# imuv1_3.net
KiCad netlist of a schematic drawn in EAGLE
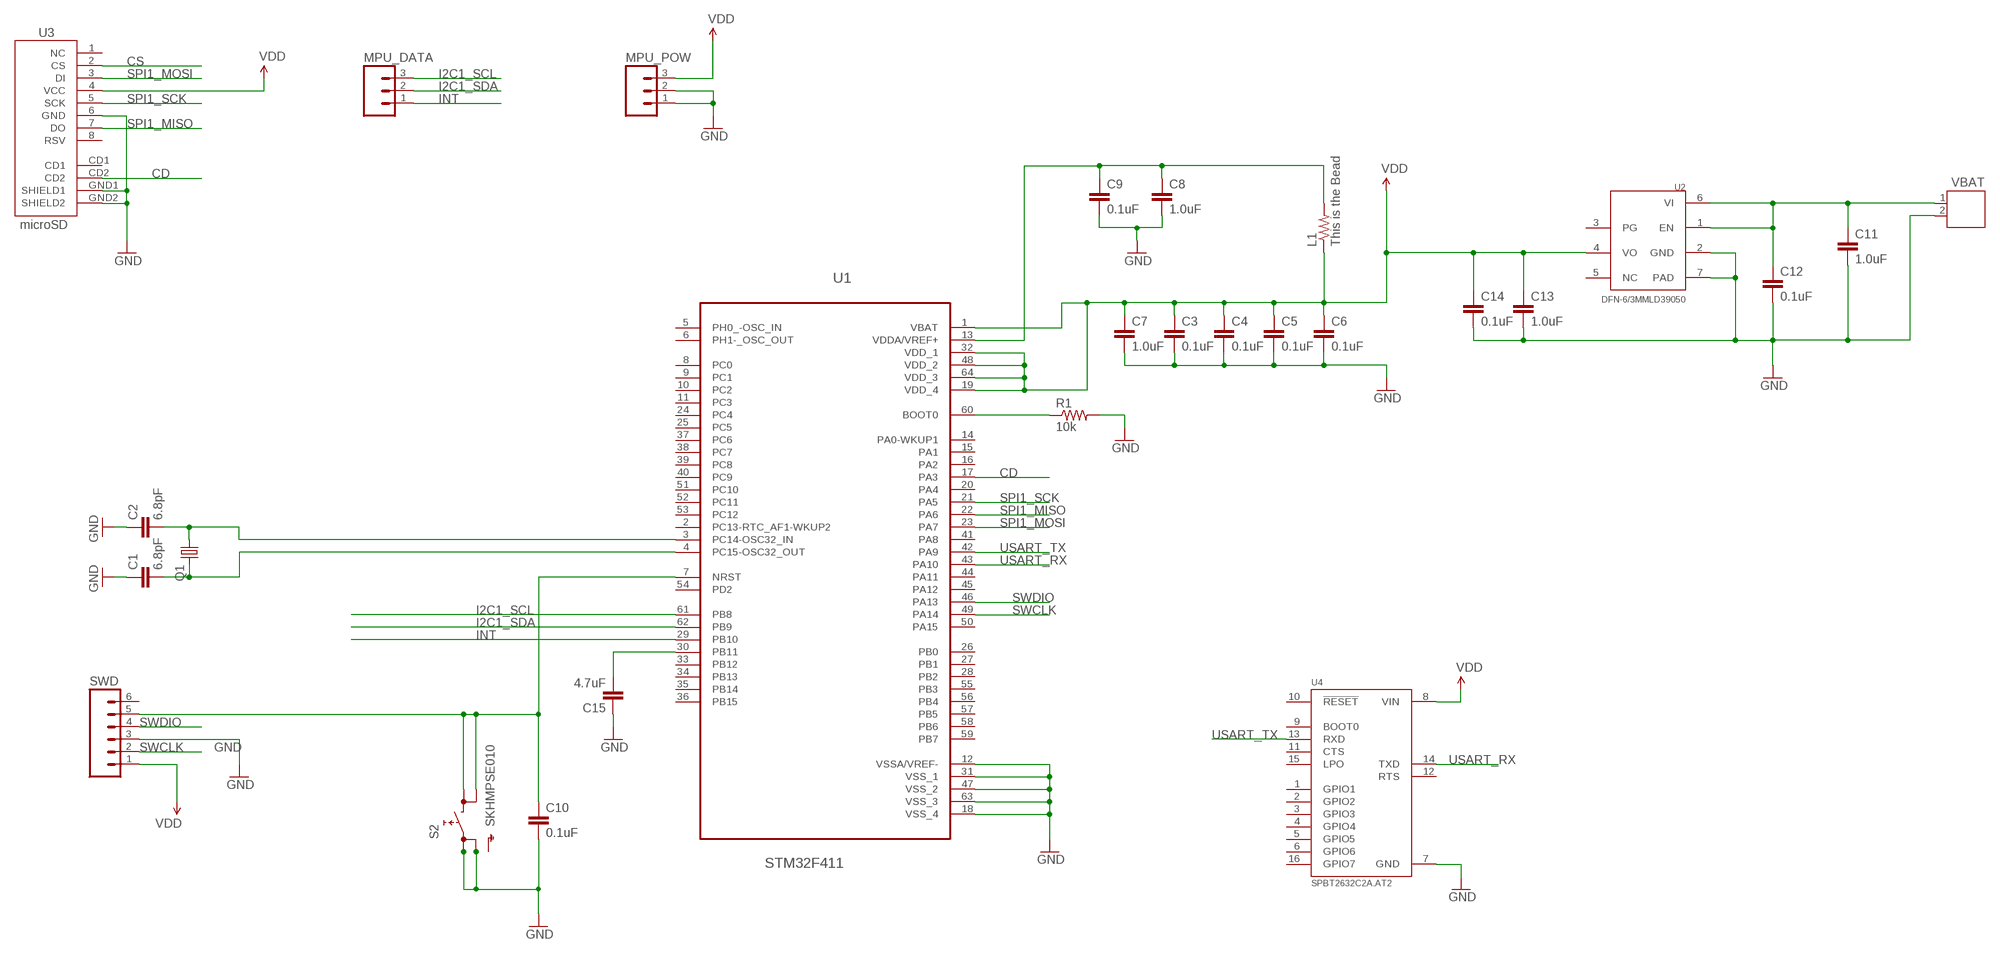
[diagram p0: schematic, sheet 1]

(export (version "E")
  (design (tool "Eeschema 10.0.6"))
  (components
    (comp (ref "C1")
      (value "6.8pF")
      (footprint "eagle-import:0603-CAP")
      (libsource (lib "eagle-import") (part "1.0PF-50V(-/+.25PF)(0603)"))
    )
    (comp (ref "C2")
      (value "6.8pF")
      (footprint "eagle-import:0603-CAP")
      (libsource (lib "eagle-import") (part "1.0PF-50V(-/+.25PF)(0603)"))
    )
    (comp (ref "C3")
      (value "0.1uF")
      (footprint "eagle-import:0603-CAP")
      (libsource (lib "eagle-import") (part "0.1UF-100V-10%(0603)"))
    )
    (comp (ref "C4")
      (value "0.1uF")
      (footprint "eagle-import:0603-CAP")
      (libsource (lib "eagle-import") (part "0.1UF-100V-10%(0603)"))
    )
    (comp (ref "C5")
      (value "0.1uF")
      (footprint "eagle-import:0603-CAP")
      (libsource (lib "eagle-import") (part "0.1UF-100V-10%(0603)"))
    )
    (comp (ref "C6")
      (value "0.1uF")
      (footprint "eagle-import:0603-CAP")
      (libsource (lib "eagle-import") (part "0.1UF-100V-10%(0603)"))
    )
    (comp (ref "C7")
      (value "1.0uF")
      (footprint "eagle-import:0603-CAP")
      (libsource (lib "eagle-import") (part "1.0UF-16V-10%(0603)"))
    )
    (comp (ref "C8")
      (value "1.0uF")
      (footprint "eagle-import:0603-CAP")
      (libsource (lib "eagle-import") (part "1.0UF-16V-10%(0603)"))
    )
    (comp (ref "C9")
      (value "0.1uF")
      (footprint "eagle-import:0603-CAP")
      (libsource (lib "eagle-import") (part "0.1UF-100V-10%(0603)"))
    )
    (comp (ref "C10")
      (value "0.1uF")
      (footprint "eagle-import:0603-CAP")
      (libsource (lib "eagle-import") (part "0.1UF-100V-10%(0603)"))
    )
    (comp (ref "C11")
      (value "1.0uF")
      (footprint "eagle-import:0603-CAP")
      (libsource (lib "eagle-import") (part "1.0UF-16V-10%(0603)"))
    )
    (comp (ref "C12")
      (value "0.1uF")
      (footprint "eagle-import:0603-CAP")
      (libsource (lib "eagle-import") (part "0.1UF-100V-10%(0603)"))
    )
    (comp (ref "C13")
      (value "1.0uF")
      (footprint "eagle-import:0603-CAP")
      (libsource (lib "eagle-import") (part "1.0UF-16V-10%(0603)"))
    )
    (comp (ref "C14")
      (value "0.1uF")
      (footprint "eagle-import:0603-CAP")
      (libsource (lib "eagle-import") (part "0.1UF-100V-10%(0603)"))
    )
    (comp (ref "C15")
      (value "4.7uF")
      (footprint "eagle-import:1206-CAP")
      (libsource (lib "eagle-import") (part "4.7UF-16V-20%,+80%-(1206)"))
    )
    (comp (ref "L1")
      (value "This is the Bead")
      (footprint "eagle-import:0603-RES")
      (libsource (lib "eagle-import") (part "1OHM1/10W1%(0603)"))
    )
    (comp (ref "MPU_DATA")
      (value "M03PTH")
      (footprint "eagle-import:1X03")
      (libsource (lib "eagle-import") (part "M03PTH"))
    )
    (comp (ref "MPU_POW")
      (value "M03PTH")
      (footprint "eagle-import:1X03")
      (libsource (lib "eagle-import") (part "M03PTH"))
    )
    (comp (ref "Q1")
      (value "CRYSTALMM20SS")
      (footprint "eagle-import:MM20SS")
      (libsource (lib "eagle-import") (part "CRYSTALMM20SS"))
    )
    (comp (ref "R1")
      (value "10k")
      (footprint "eagle-import:0603-RES")
      (libsource (lib "eagle-import") (part "470OHM1/10W1%(0603)"))
    )
    (comp (ref "S2")
      (value "SKHMPSE010")
      (footprint "eagle-import:SKHMPXE010")
      (libsource (lib "eagle-import") (part "SKHMPE010S"))
    )
    (comp (ref "SWD")
      (value "M06SILK_FEMALE_PTH")
      (footprint "eagle-import:1X06")
      (libsource (lib "eagle-import") (part "M06SILK_FEMALE_PTH"))
    )
    (comp (ref "U1")
      (value "STM32F411")
      (footprint "eagle-import:QFP50P1200X1200X160-64N")
      (libsource (lib "eagle-import") (part "STM32L152RBT6STM32F411"))
    )
    (comp (ref "U2")
      (value "DFN-6/3MMLD39050")
      (footprint "eagle-import:DFN-6_3MM")
      (libsource (lib "eagle-import") (part "DFN-6/3MMLD39050"))
    )
    (comp (ref "U3")
      (value "microSD")
      (footprint "eagle-import:MICRO-SD-SOCKET-PP")
      (libsource (lib "eagle-import") (part "USD-SOCKETSMD"))
    )
    (comp (ref "U4")
      (value "SPBT2632C2A.AT2")
      (footprint "eagle-import:XCVR_SPBT2632C2A.AT2")
      (libsource (lib "eagle-import") (part "SPBT2632C2A.AT2"))
    )
    (comp (ref "VBAT")
      (value "JST-PH2")
      (footprint "eagle-import:JST-PH2")
      (libsource (lib "eagle-import") (part "JST-PH2"))
    )
  )
  (nets
    (net (code "1") (name "/CD") (class "Default")
      (node (ref "U1") (pin "17") (pinfunction "PA3_17") (pintype "bidirectional"))
      (node (ref "U3") (pin "CD2") (pinfunction "CD2_CD2") (pintype "bidirectional"))
    )
    (net (code "2") (name "/CS") (class "Default")
      (node (ref "U3") (pin "2") (pinfunction "CS_2") (pintype "bidirectional"))
    )
    (net (code "3") (name "/I2C1_SCL") (class "Default")
      (node (ref "MPU_DATA") (pin "3") (pinfunction "3_3") (pintype "passive"))
      (node (ref "U1") (pin "61") (pinfunction "PB8_61") (pintype "bidirectional"))
    )
    (net (code "4") (name "/I2C1_SDA") (class "Default")
      (node (ref "MPU_DATA") (pin "2") (pinfunction "2_2") (pintype "passive"))
      (node (ref "U1") (pin "62") (pinfunction "PB9_62") (pintype "bidirectional"))
    )
    (net (code "5") (name "/INT") (class "Default")
      (node (ref "MPU_DATA") (pin "1") (pinfunction "1_1") (pintype "passive"))
      (node (ref "U1") (pin "29") (pinfunction "PB10_29") (pintype "bidirectional"))
    )
    (net (code "6") (name "/NC") (class "Default")
      (node (ref "U2") (pin "5") (pinfunction "NC_5") (pintype "power_in"))
    )
    (net (code "7") (name "/PG") (class "Default")
      (node (ref "U2") (pin "3") (pinfunction "PG_3") (pintype "power_in"))
    )
    (net (code "8") (name "/SPI1_MISO") (class "Default")
      (node (ref "U1") (pin "22") (pinfunction "PA6_22") (pintype "bidirectional"))
      (node (ref "U3") (pin "7") (pinfunction "DO_7") (pintype "bidirectional"))
    )
    (net (code "9") (name "/SPI1_MOSI") (class "Default")
      (node (ref "U1") (pin "23") (pinfunction "PA7_23") (pintype "bidirectional"))
      (node (ref "U3") (pin "3") (pinfunction "DI_3") (pintype "bidirectional"))
    )
    (net (code "10") (name "/SPI1_SCK") (class "Default")
      (node (ref "U1") (pin "21") (pinfunction "PA5_21") (pintype "bidirectional"))
      (node (ref "U3") (pin "5") (pinfunction "SCK_5") (pintype "bidirectional"))
    )
    (net (code "11") (name "/SWCLK") (class "Default")
      (node (ref "SWD") (pin "2") (pinfunction "2_2") (pintype "passive"))
      (node (ref "U1") (pin "49") (pinfunction "PA14_49") (pintype "bidirectional"))
    )
    (net (code "12") (name "/SWDIO") (class "Default")
      (node (ref "SWD") (pin "4") (pinfunction "4_4") (pintype "passive"))
      (node (ref "U1") (pin "46") (pinfunction "PA13_46") (pintype "bidirectional"))
    )
    (net (code "13") (name "/USART_RX") (class "Default")
      (node (ref "U1") (pin "43") (pinfunction "PA10_43") (pintype "bidirectional"))
      (node (ref "U4") (pin "14") (pinfunction "TXD_14") (pintype "output"))
    )
    (net (code "14") (name "/USART_TX") (class "Default")
      (node (ref "U1") (pin "42") (pinfunction "PA9_42") (pintype "bidirectional"))
      (node (ref "U4") (pin "13") (pinfunction "RXD_13") (pintype "input"))
    )
    (net (code "15") (name "GND") (class "Default")
      (node (ref "C1") (pin "1") (pinfunction "1_1") (pintype "passive"))
      (node (ref "C10") (pin "2") (pinfunction "2_2") (pintype "passive"))
      (node (ref "C11") (pin "2") (pinfunction "2_2") (pintype "passive"))
      (node (ref "C12") (pin "2") (pinfunction "2_2") (pintype "passive"))
      (node (ref "C13") (pin "2") (pinfunction "2_2") (pintype "passive"))
      (node (ref "C14") (pin "2") (pinfunction "2_2") (pintype "passive"))
      (node (ref "C15") (pin "1") (pinfunction "1_1") (pintype "passive"))
      (node (ref "C2") (pin "1") (pinfunction "1_1") (pintype "passive"))
      (node (ref "C3") (pin "2") (pinfunction "2_2") (pintype "passive"))
      (node (ref "C4") (pin "2") (pinfunction "2_2") (pintype "passive"))
      (node (ref "C5") (pin "2") (pinfunction "2_2") (pintype "passive"))
      (node (ref "C6") (pin "2") (pinfunction "2_2") (pintype "passive"))
      (node (ref "C7") (pin "2") (pinfunction "2_2") (pintype "passive"))
      (node (ref "C8") (pin "2") (pinfunction "2_2") (pintype "passive"))
      (node (ref "C9") (pin "2") (pinfunction "2_2") (pintype "passive"))
      (node (ref "MPU_POW") (pin "1") (pinfunction "1_1") (pintype "passive"))
      (node (ref "MPU_POW") (pin "2") (pinfunction "2_2") (pintype "passive"))
      (node (ref "R1") (pin "2") (pinfunction "2_2") (pintype "passive"))
      (node (ref "S2") (pin "1") (pinfunction "1.1_1") (pintype "passive"))
      (node (ref "S2") (pin "2") (pinfunction "1.2_2") (pintype "passive"))
      (node (ref "SWD") (pin "3") (pinfunction "3_3") (pintype "passive"))
      (node (ref "U1") (pin "12") (pinfunction "VSSA/VREF-_12") (pintype "power_in"))
      (node (ref "U1") (pin "18") (pinfunction "VSS_4_18") (pintype "power_in"))
      (node (ref "U1") (pin "31") (pinfunction "VSS_1_31") (pintype "power_in"))
      (node (ref "U1") (pin "47") (pinfunction "VSS_2_47") (pintype "power_in"))
      (node (ref "U1") (pin "63") (pinfunction "VSS_3_63") (pintype "power_in"))
      (node (ref "U2") (pin "2") (pinfunction "GND_2") (pintype "power_in"))
      (node (ref "U2") (pin "7") (pinfunction "PAD_7") (pintype "power_in"))
      (node (ref "U3") (pin "6") (pinfunction "GND_6") (pintype "bidirectional"))
      (node (ref "U3") (pin "GND1") (pinfunction "SHIELD1_GND1") (pintype "bidirectional"))
      (node (ref "U3") (pin "GND2") (pinfunction "SHIELD2_GND2") (pintype "bidirectional"))
      (node (ref "U4") (pin "7") (pinfunction "GND_7") (pintype "power_in"))
      (node (ref "VBAT") (pin "2") (pinfunction "2_2") (pintype "passive"))
    )
    (net (code "16") (name "Net-(Q1-2)") (class "Default")
      (node (ref "C1") (pin "2") (pinfunction "2_2") (pintype "passive"))
      (node (ref "Q1") (pin "4") (pinfunction "2_4") (pintype "passive"))
      (node (ref "U1") (pin "4") (pinfunction "PC15-OSC32_OUT_4") (pintype "bidirectional"))
    )
    (net (code "17") (name "Net-(S2-2.1)") (class "Default")
      (node (ref "C10") (pin "1") (pinfunction "1_1") (pintype "passive"))
      (node (ref "S2") (pin "3") (pinfunction "2.1_3") (pintype "passive"))
      (node (ref "S2") (pin "4") (pinfunction "2.2_4") (pintype "passive"))
      (node (ref "SWD") (pin "5") (pinfunction "5_5") (pintype "passive"))
      (node (ref "U1") (pin "7") (pinfunction "NRST_7") (pintype "bidirectional"))
    )
    (net (code "18") (name "Net-(U1-BOOT0)") (class "Default")
      (node (ref "R1") (pin "1") (pinfunction "1_1") (pintype "passive"))
      (node (ref "U1") (pin "60") (pinfunction "BOOT0_60") (pintype "input"))
    )
    (net (code "19") (name "Net-(U1-PB11)") (class "Default")
      (node (ref "C15") (pin "2") (pinfunction "2_2") (pintype "passive"))
      (node (ref "U1") (pin "30") (pinfunction "PB11_30") (pintype "bidirectional"))
    )
    (net (code "20") (name "Net-(U1-PC14-OSC32_IN)") (class "Default")
      (node (ref "C2") (pin "2") (pinfunction "2_2") (pintype "passive"))
      (node (ref "Q1") (pin "1") (pinfunction "1_1") (pintype "passive"))
      (node (ref "U1") (pin "3") (pinfunction "PC14-OSC32_IN_3") (pintype "bidirectional"))
    )
    (net (code "21") (name "Net-(U1-VDDA{slash}VREF+)") (class "Default")
      (node (ref "C8") (pin "1") (pinfunction "1_1") (pintype "passive"))
      (node (ref "C9") (pin "1") (pinfunction "1_1") (pintype "passive"))
      (node (ref "L1") (pin "2") (pinfunction "2_2") (pintype "passive"))
      (node (ref "U1") (pin "13") (pinfunction "VDDA/VREF+_13") (pintype "power_in"))
    )
    (net (code "22") (name "Net-(U2-EN)") (class "Default")
      (node (ref "C11") (pin "1") (pinfunction "1_1") (pintype "passive"))
      (node (ref "C12") (pin "1") (pinfunction "1_1") (pintype "passive"))
      (node (ref "U2") (pin "1") (pinfunction "EN_1") (pintype "power_in"))
      (node (ref "U2") (pin "6") (pinfunction "VI_6") (pintype "power_in"))
      (node (ref "VBAT") (pin "1") (pinfunction "1_1") (pintype "passive"))
    )
    (net (code "23") (name "VDD") (class "Default")
      (node (ref "C13") (pin "1") (pinfunction "1_1") (pintype "passive"))
      (node (ref "C14") (pin "1") (pinfunction "1_1") (pintype "passive"))
      (node (ref "C3") (pin "1") (pinfunction "1_1") (pintype "passive"))
      (node (ref "C4") (pin "1") (pinfunction "1_1") (pintype "passive"))
      (node (ref "C5") (pin "1") (pinfunction "1_1") (pintype "passive"))
      (node (ref "C6") (pin "1") (pinfunction "1_1") (pintype "passive"))
      (node (ref "C7") (pin "1") (pinfunction "1_1") (pintype "passive"))
      (node (ref "L1") (pin "1") (pinfunction "1_1") (pintype "passive"))
      (node (ref "MPU_POW") (pin "3") (pinfunction "3_3") (pintype "passive"))
      (node (ref "SWD") (pin "1") (pinfunction "1_1") (pintype "passive"))
      (node (ref "U1") (pin "1") (pinfunction "VBAT_1") (pintype "power_in"))
      (node (ref "U1") (pin "19") (pinfunction "VDD_4_19") (pintype "power_in"))
      (node (ref "U1") (pin "32") (pinfunction "VDD_1_32") (pintype "power_in"))
      (node (ref "U1") (pin "48") (pinfunction "VDD_2_48") (pintype "power_in"))
      (node (ref "U1") (pin "64") (pinfunction "VDD_3_64") (pintype "power_in"))
      (node (ref "U2") (pin "4") (pinfunction "VO_4") (pintype "power_in"))
      (node (ref "U3") (pin "4") (pinfunction "VCC_4") (pintype "bidirectional"))
      (node (ref "U4") (pin "8") (pinfunction "VIN_8") (pintype "power_in"))
    )
    (net (code "24") (name "unconnected-(S2-SH-Pad5)") (class "Default")
      (node (ref "S2") (pin "5") (pinfunction "SH_5") (pintype "passive"))
    )
    (net (code "25") (name "unconnected-(SWD-Pad6)") (class "Default")
      (node (ref "SWD") (pin "6") (pinfunction "6_6") (pintype "passive"))
    )
    (net (code "26") (name "unconnected-(U1-PA0-WKUP1-Pad14)") (class "Default")
      (node (ref "U1") (pin "14") (pinfunction "PA0-WKUP1_14") (pintype "bidirectional"))
    )
    (net (code "27") (name "unconnected-(U1-PA1-Pad15)") (class "Default")
      (node (ref "U1") (pin "15") (pinfunction "PA1_15") (pintype "bidirectional"))
    )
    (net (code "28") (name "unconnected-(U1-PA2-Pad16)") (class "Default")
      (node (ref "U1") (pin "16") (pinfunction "PA2_16") (pintype "bidirectional"))
    )
    (net (code "29") (name "unconnected-(U1-PA4-Pad20)") (class "Default")
      (node (ref "U1") (pin "20") (pinfunction "PA4_20") (pintype "bidirectional"))
    )
    (net (code "30") (name "unconnected-(U1-PA8-Pad41)") (class "Default")
      (node (ref "U1") (pin "41") (pinfunction "PA8_41") (pintype "bidirectional"))
    )
    (net (code "31") (name "unconnected-(U1-PA11-Pad44)") (class "Default")
      (node (ref "U1") (pin "44") (pinfunction "PA11_44") (pintype "bidirectional"))
    )
    (net (code "32") (name "unconnected-(U1-PA12-Pad45)") (class "Default")
      (node (ref "U1") (pin "45") (pinfunction "PA12_45") (pintype "bidirectional"))
    )
    (net (code "33") (name "unconnected-(U1-PA15-Pad50)") (class "Default")
      (node (ref "U1") (pin "50") (pinfunction "PA15_50") (pintype "bidirectional"))
    )
    (net (code "34") (name "unconnected-(U1-PB0-Pad26)") (class "Default")
      (node (ref "U1") (pin "26") (pinfunction "PB0_26") (pintype "bidirectional"))
    )
    (net (code "35") (name "unconnected-(U1-PB1-Pad27)") (class "Default")
      (node (ref "U1") (pin "27") (pinfunction "PB1_27") (pintype "bidirectional"))
    )
    (net (code "36") (name "unconnected-(U1-PB2-Pad28)") (class "Default")
      (node (ref "U1") (pin "28") (pinfunction "PB2_28") (pintype "bidirectional"))
    )
    (net (code "37") (name "unconnected-(U1-PB3-Pad55)") (class "Default")
      (node (ref "U1") (pin "55") (pinfunction "PB3_55") (pintype "bidirectional"))
    )
    (net (code "38") (name "unconnected-(U1-PB4-Pad56)") (class "Default")
      (node (ref "U1") (pin "56") (pinfunction "PB4_56") (pintype "bidirectional"))
    )
    (net (code "39") (name "unconnected-(U1-PB5-Pad57)") (class "Default")
      (node (ref "U1") (pin "57") (pinfunction "PB5_57") (pintype "bidirectional"))
    )
    (net (code "40") (name "unconnected-(U1-PB6-Pad58)") (class "Default")
      (node (ref "U1") (pin "58") (pinfunction "PB6_58") (pintype "bidirectional"))
    )
    (net (code "41") (name "unconnected-(U1-PB7-Pad59)") (class "Default")
      (node (ref "U1") (pin "59") (pinfunction "PB7_59") (pintype "bidirectional"))
    )
    (net (code "42") (name "unconnected-(U1-PB12-Pad33)") (class "Default")
      (node (ref "U1") (pin "33") (pinfunction "PB12_33") (pintype "bidirectional"))
    )
    (net (code "43") (name "unconnected-(U1-PB13-Pad34)") (class "Default")
      (node (ref "U1") (pin "34") (pinfunction "PB13_34") (pintype "bidirectional"))
    )
    (net (code "44") (name "unconnected-(U1-PB14-Pad35)") (class "Default")
      (node (ref "U1") (pin "35") (pinfunction "PB14_35") (pintype "bidirectional"))
    )
    (net (code "45") (name "unconnected-(U1-PB15-Pad36)") (class "Default")
      (node (ref "U1") (pin "36") (pinfunction "PB15_36") (pintype "bidirectional"))
    )
    (net (code "46") (name "unconnected-(U1-PC0-Pad8)") (class "Default")
      (node (ref "U1") (pin "8") (pinfunction "PC0_8") (pintype "bidirectional"))
    )
    (net (code "47") (name "unconnected-(U1-PC1-Pad9)") (class "Default")
      (node (ref "U1") (pin "9") (pinfunction "PC1_9") (pintype "bidirectional"))
    )
    (net (code "48") (name "unconnected-(U1-PC2-Pad10)") (class "Default")
      (node (ref "U1") (pin "10") (pinfunction "PC2_10") (pintype "bidirectional"))
    )
    (net (code "49") (name "unconnected-(U1-PC3-Pad11)") (class "Default")
      (node (ref "U1") (pin "11") (pinfunction "PC3_11") (pintype "bidirectional"))
    )
    (net (code "50") (name "unconnected-(U1-PC4-Pad24)") (class "Default")
      (node (ref "U1") (pin "24") (pinfunction "PC4_24") (pintype "bidirectional"))
    )
    (net (code "51") (name "unconnected-(U1-PC5-Pad25)") (class "Default")
      (node (ref "U1") (pin "25") (pinfunction "PC5_25") (pintype "bidirectional"))
    )
    (net (code "52") (name "unconnected-(U1-PC6-Pad37)") (class "Default")
      (node (ref "U1") (pin "37") (pinfunction "PC6_37") (pintype "bidirectional"))
    )
    (net (code "53") (name "unconnected-(U1-PC7-Pad38)") (class "Default")
      (node (ref "U1") (pin "38") (pinfunction "PC7_38") (pintype "bidirectional"))
    )
    (net (code "54") (name "unconnected-(U1-PC8-Pad39)") (class "Default")
      (node (ref "U1") (pin "39") (pinfunction "PC8_39") (pintype "bidirectional"))
    )
    (net (code "55") (name "unconnected-(U1-PC9-Pad40)") (class "Default")
      (node (ref "U1") (pin "40") (pinfunction "PC9_40") (pintype "bidirectional"))
    )
    (net (code "56") (name "unconnected-(U1-PC10-Pad51)") (class "Default")
      (node (ref "U1") (pin "51") (pinfunction "PC10_51") (pintype "bidirectional"))
    )
    (net (code "57") (name "unconnected-(U1-PC11-Pad52)") (class "Default")
      (node (ref "U1") (pin "52") (pinfunction "PC11_52") (pintype "bidirectional"))
    )
    (net (code "58") (name "unconnected-(U1-PC12-Pad53)") (class "Default")
      (node (ref "U1") (pin "53") (pinfunction "PC12_53") (pintype "bidirectional"))
    )
    (net (code "59") (name "unconnected-(U1-PC13-RTC_AF1-WKUP2-Pad2)") (class "Default")
      (node (ref "U1") (pin "2") (pinfunction "PC13-RTC_AF1-WKUP2_2") (pintype "bidirectional"))
    )
    (net (code "60") (name "unconnected-(U1-PD2-Pad54)") (class "Default")
      (node (ref "U1") (pin "54") (pinfunction "PD2_54") (pintype "bidirectional"))
    )
    (net (code "61") (name "unconnected-(U1-PH0_-OSC_IN-Pad5)") (class "Default")
      (node (ref "U1") (pin "5") (pinfunction "PH0_-OSC_IN_5") (pintype "bidirectional"))
    )
    (net (code "62") (name "unconnected-(U1-PH1-_OSC_OUT-Pad6)") (class "Default")
      (node (ref "U1") (pin "6") (pinfunction "PH1-_OSC_OUT_6") (pintype "bidirectional"))
    )
    (net (code "63") (name "unconnected-(U3-NC-Pad1)") (class "Default")
      (node (ref "U3") (pin "1") (pinfunction "NC_1") (pintype "bidirectional"))
    )
    (net (code "64") (name "unconnected-(U3-PadCD1)") (class "Default")
      (node (ref "U3") (pin "CD1") (pinfunction "CD1_CD1") (pintype "bidirectional"))
    )
    (net (code "65") (name "unconnected-(U3-RSV-Pad8)") (class "Default")
      (node (ref "U3") (pin "8") (pinfunction "RSV_8") (pintype "bidirectional"))
    )
    (net (code "66") (name "unconnected-(U4-BOOT0-Pad9)") (class "Default")
      (node (ref "U4") (pin "9") (pinfunction "BOOT0_9") (pintype "input"))
    )
    (net (code "67") (name "unconnected-(U4-CTS-Pad11)") (class "Default")
      (node (ref "U4") (pin "11") (pinfunction "CTS_11") (pintype "input"))
    )
    (net (code "68") (name "unconnected-(U4-GPIO1-Pad1)") (class "Default")
      (node (ref "U4") (pin "1") (pinfunction "GPIO1_1") (pintype "bidirectional"))
    )
    (net (code "69") (name "unconnected-(U4-GPIO2-Pad2)") (class "Default")
      (node (ref "U4") (pin "2") (pinfunction "GPIO2_2") (pintype "bidirectional"))
    )
    (net (code "70") (name "unconnected-(U4-GPIO3-Pad3)") (class "Default")
      (node (ref "U4") (pin "3") (pinfunction "GPIO3_3") (pintype "bidirectional"))
    )
    (net (code "71") (name "unconnected-(U4-GPIO4-Pad4)") (class "Default")
      (node (ref "U4") (pin "4") (pinfunction "GPIO4_4") (pintype "bidirectional"))
    )
    (net (code "72") (name "unconnected-(U4-GPIO5-Pad5)") (class "Default")
      (node (ref "U4") (pin "5") (pinfunction "GPIO5_5") (pintype "bidirectional"))
    )
    (net (code "73") (name "unconnected-(U4-GPIO6-Pad6)") (class "Default")
      (node (ref "U4") (pin "6") (pinfunction "GPIO6_6") (pintype "bidirectional"))
    )
    (net (code "74") (name "unconnected-(U4-GPIO7-Pad16)") (class "Default")
      (node (ref "U4") (pin "16") (pinfunction "GPIO7_16") (pintype "bidirectional"))
    )
    (net (code "75") (name "unconnected-(U4-LPO-Pad15)") (class "Default")
      (node (ref "U4") (pin "15") (pinfunction "LPO_15") (pintype "input"))
    )
    (net (code "76") (name "unconnected-(U4-RTS-Pad12)") (class "Default")
      (node (ref "U4") (pin "12") (pinfunction "RTS_12") (pintype "output"))
    )
    (net (code "77") (name "unconnected-(U4-~{RESET}-Pad10)") (class "Default")
      (node (ref "U4") (pin "10") (pinfunction "~{RESET}_10") (pintype "input"))
    )
  )
)
